# iya_ini_pcb_cetaknya.net
KiCad netlist of a schematic drawn in EAGLE
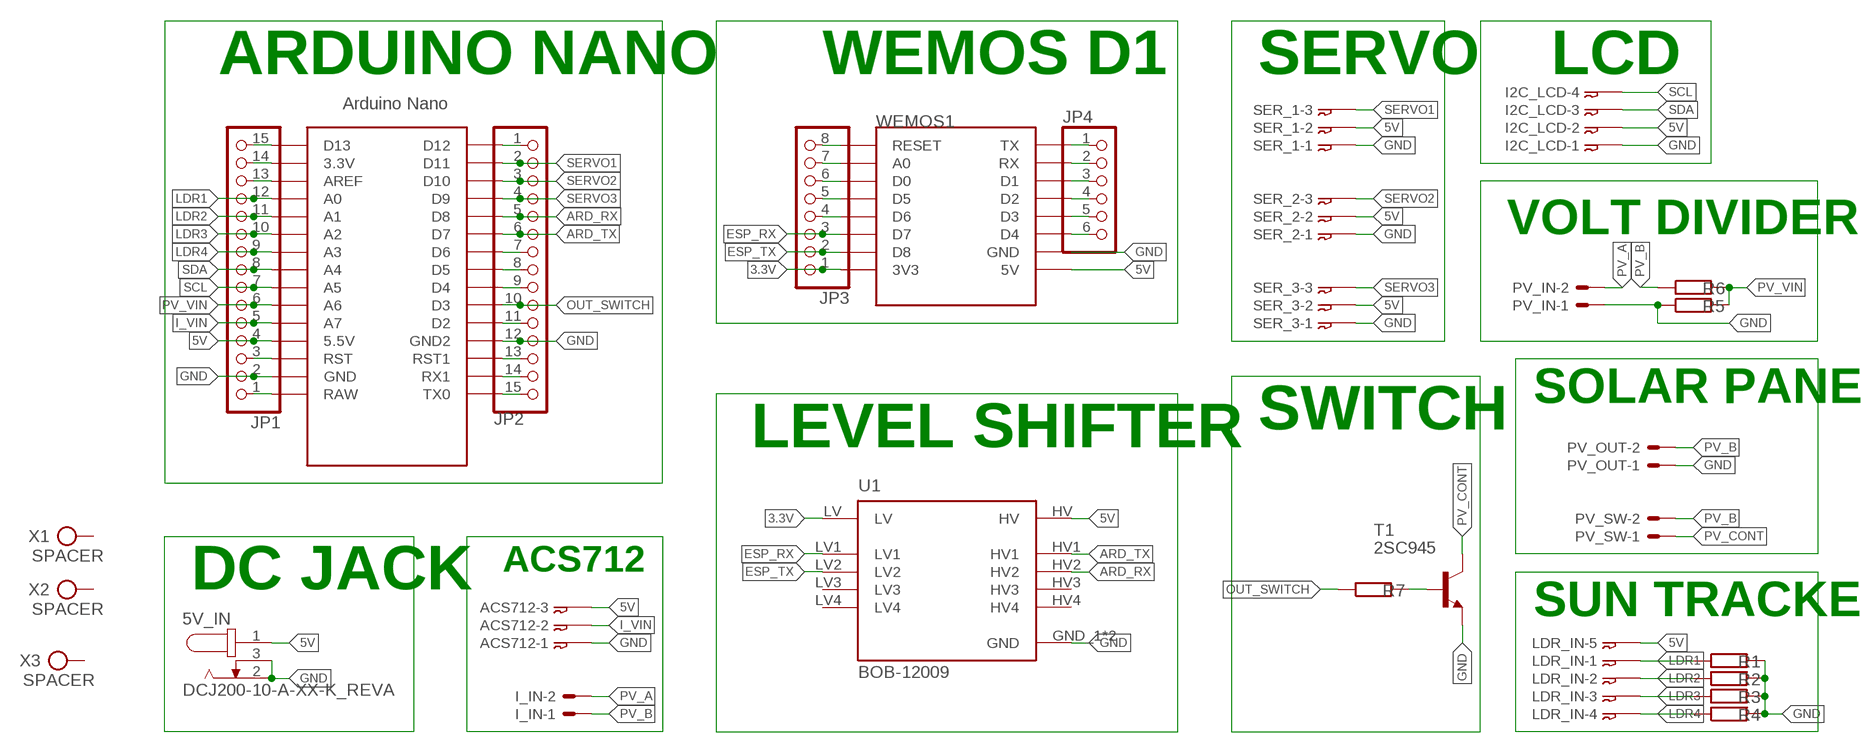
[diagram p0: schematic, sheet 1]

(export (version "E")
  (design (tool "Eeschema 10.0.6"))
  (components
    (comp (ref "5V_IN")
      (value "DCJ200-10-A-XX-K_REVA")
      (footprint "eagle-import:GCT_DCJ200-10-A-XX-K_REVA")
      (fields (field (name "MF") "Global Connector Technology") (field (name "MP") "DCJ200-10-A-K1-K"))
      (libsource (lib "eagle-import") (part "DCJ200-10-A-XX-K_REVA"))
    )
    (comp (ref "ACS712")
      (value "03-JST-B3B-XH-A")
      (footprint "eagle-import:B3B-XH")
      (libsource (lib "eagle-import") (part "03-JST-B3B-XH-A"))
    )
    (comp (ref "I2C_LCD")
      (value "04-JST-B4B-XH-A")
      (footprint "eagle-import:B4B-XH")
      (libsource (lib "eagle-import") (part "04-JST-B4B-XH-A"))
    )
    (comp (ref "I_IN")
      (value "MOLEX_2P_27-2021")
      (footprint "eagle-import:6410-02")
      (fields (field (name "MF") "MOLEX"))
      (libsource (lib "eagle-import") (part "MOLEX_2P_27-2021"))
    )
    (comp (ref "JP1")
      (value "PINHD-1X15")
      (footprint "eagle-import:1X15")
      (libsource (lib "eagle-import") (part "PINHD-1X15"))
    )
    (comp (ref "JP2")
      (value "PINHD-1X15")
      (footprint "eagle-import:1X15")
      (libsource (lib "eagle-import") (part "PINHD-1X15"))
    )
    (comp (ref "JP3")
      (value "PINHD-1X8")
      (footprint "eagle-import:1X08")
      (libsource (lib "eagle-import") (part "PINHD-1X8"))
    )
    (comp (ref "JP4")
      (value "PINHD-1X6")
      (footprint "eagle-import:1X06")
      (libsource (lib "eagle-import") (part "PINHD-1X6"))
    )
    (comp (ref "LDR_IN")
      (value "05-JST-B5B-XH-A")
      (footprint "eagle-import:B5B-XH")
      (libsource (lib "eagle-import") (part "05-JST-B5B-XH-A"))
    )
    (comp (ref "PV_IN")
      (value "MOLEX_2P_27-2021")
      (footprint "eagle-import:6410-02")
      (fields (field (name "MF") "MOLEX"))
      (libsource (lib "eagle-import") (part "MOLEX_2P_27-2021"))
    )
    (comp (ref "PV_OUT")
      (value "MOLEX_2P_27-2021")
      (footprint "eagle-import:6410-02")
      (fields (field (name "MF") "MOLEX"))
      (libsource (lib "eagle-import") (part "MOLEX_2P_27-2021"))
    )
    (comp (ref "PV_SW")
      (value "MOLEX_2P_27-2021")
      (footprint "eagle-import:6410-02")
      (fields (field (name "MF") "MOLEX"))
      (libsource (lib "eagle-import") (part "MOLEX_2P_27-2021"))
    )
    (comp (ref "R1")
      (value "R-EU_0207/2V")
      (footprint "eagle-import:0207_2V")
      (libsource (lib "eagle-import") (part "R-EU_0207/2V"))
    )
    (comp (ref "R2")
      (value "R-EU_0207/2V")
      (footprint "eagle-import:0207_2V")
      (libsource (lib "eagle-import") (part "R-EU_0207/2V"))
    )
    (comp (ref "R3")
      (value "R-EU_0207/2V")
      (footprint "eagle-import:0207_2V")
      (libsource (lib "eagle-import") (part "R-EU_0207/2V"))
    )
    (comp (ref "R4")
      (value "R-EU_0207/2V")
      (footprint "eagle-import:0207_2V")
      (libsource (lib "eagle-import") (part "R-EU_0207/2V"))
    )
    (comp (ref "R5")
      (value "R-EU_0207/10")
      (footprint "eagle-import:0207_10")
      (libsource (lib "eagle-import") (part "R-EU_0207/10"))
    )
    (comp (ref "R6")
      (value "R-EU_0207/10")
      (footprint "eagle-import:0207_10")
      (libsource (lib "eagle-import") (part "R-EU_0207/10"))
    )
    (comp (ref "R7")
      (value "R-EU_0207/10")
      (footprint "eagle-import:0207_10")
      (libsource (lib "eagle-import") (part "R-EU_0207/10"))
    )
    (comp (ref "SER_1")
      (value "03-JST-B3B-XH-A")
      (footprint "eagle-import:B3B-XH")
      (libsource (lib "eagle-import") (part "03-JST-B3B-XH-A"))
    )
    (comp (ref "SER_2")
      (value "03-JST-B3B-XH-A")
      (footprint "eagle-import:B3B-XH")
      (libsource (lib "eagle-import") (part "03-JST-B3B-XH-A"))
    )
    (comp (ref "SER_3")
      (value "03-JST-B3B-XH-A")
      (footprint "eagle-import:B3B-XH")
      (libsource (lib "eagle-import") (part "03-JST-B3B-XH-A"))
    )
    (comp (ref "T1")
      (value "2SC945")
      (footprint "eagle-import:TO92-ECB")
      (libsource (lib "eagle-import") (part "2SC945"))
    )
    (comp (ref "U$1")
      (value "NANO")
      (footprint "eagle-import:NANO")
      (libsource (lib "eagle-import") (part "NANO"))
    )
    (comp (ref "U1")
      (value "BOB-12009")
      (footprint "eagle-import:CONV_BOB-12009")
      (fields (field (name "MF") "SparkFun"))
      (libsource (lib "eagle-import") (part "BOB-12009"))
    )
    (comp (ref "WEMOS1")
      (value "WEMOS-D1-MINI")
      (footprint "eagle-import:WEMOS-D1-MINI")
      (libsource (lib "eagle-import") (part "WEMOS-D1-MINI"))
    )
    (comp (ref "X1")
      (value "SPACER")
      (footprint "eagle-import:SPACER")
      (libsource (lib "eagle-import") (part "SPACER"))
    )
    (comp (ref "X2")
      (value "SPACER")
      (footprint "eagle-import:SPACER")
      (libsource (lib "eagle-import") (part "SPACER"))
    )
    (comp (ref "X3")
      (value "SPACER")
      (footprint "eagle-import:SPACER")
      (libsource (lib "eagle-import") (part "SPACER"))
    )
  )
  (nets
    (net (code "1") (name "3.3V") (class "Default")
      (node (ref "JP3") (pin "1") (pinfunction "1_1") (pintype "passive"))
      (node (ref "U1") (pin "LV") (pinfunction "LV_LV") (pintype "bidirectional"))
      (node (ref "WEMOS1") (pin "3V3") (pinfunction "3V3_3V3") (pintype "bidirectional"))
    )
    (net (code "2") (name "5V") (class "Default")
      (node (ref "5V_IN") (pin "1") (pinfunction "1_1") (pintype "passive"))
      (node (ref "ACS712") (pin "P$3") (pinfunction "1_P$3") (pintype "passive"))
      (node (ref "I2C_LCD") (pin "P$2") (pinfunction "1_P$2") (pintype "passive"))
      (node (ref "JP1") (pin "4") (pinfunction "4_4") (pintype "passive"))
      (node (ref "LDR_IN") (pin "P$5") (pinfunction "1_P$5") (pintype "passive"))
      (node (ref "SER_1") (pin "P$2") (pinfunction "1_P$2") (pintype "passive"))
      (node (ref "SER_2") (pin "P$2") (pinfunction "1_P$2") (pintype "passive"))
      (node (ref "SER_3") (pin "P$2") (pinfunction "1_P$2") (pintype "passive"))
      (node (ref "U$1") (pin "5V") (pinfunction "5.5V_5V") (pintype "bidirectional"))
      (node (ref "U1") (pin "HV") (pinfunction "HV_HV") (pintype "bidirectional"))
      (node (ref "WEMOS1") (pin "5V") (pinfunction "5V_5V") (pintype "bidirectional"))
    )
    (net (code "3") (name "ARD_RX") (class "Default")
      (node (ref "JP2") (pin "5") (pinfunction "5_5") (pintype "passive"))
      (node (ref "U$1") (pin "D8") (pinfunction "D8_D8") (pintype "bidirectional"))
      (node (ref "U1") (pin "HV2") (pinfunction "HV2_HV2") (pintype "bidirectional"))
    )
    (net (code "4") (name "ARD_TX") (class "Default")
      (node (ref "JP2") (pin "6") (pinfunction "6_6") (pintype "passive"))
      (node (ref "U$1") (pin "D7") (pinfunction "D7_D7") (pintype "bidirectional"))
      (node (ref "U1") (pin "HV1") (pinfunction "HV1_HV1") (pintype "bidirectional"))
    )
    (net (code "5") (name "ESP_RX") (class "Default")
      (node (ref "JP3") (pin "3") (pinfunction "3_3") (pintype "passive"))
      (node (ref "U1") (pin "LV1") (pinfunction "LV1_LV1") (pintype "bidirectional"))
      (node (ref "WEMOS1") (pin "D7") (pinfunction "D7_D7") (pintype "bidirectional"))
    )
    (net (code "6") (name "ESP_TX") (class "Default")
      (node (ref "JP3") (pin "2") (pinfunction "2_2") (pintype "passive"))
      (node (ref "U1") (pin "LV2") (pinfunction "LV2_LV2") (pintype "bidirectional"))
      (node (ref "WEMOS1") (pin "D8") (pinfunction "D8_D8") (pintype "bidirectional"))
    )
    (net (code "7") (name "GND") (class "Default")
      (node (ref "5V_IN") (pin "2") (pinfunction "2_2") (pintype "passive"))
      (node (ref "5V_IN") (pin "3") (pinfunction "3_3") (pintype "passive"))
      (node (ref "ACS712") (pin "P$1") (pinfunction "1_P$1") (pintype "passive"))
      (node (ref "I2C_LCD") (pin "P$1") (pinfunction "1_P$1") (pintype "passive"))
      (node (ref "JP1") (pin "2") (pinfunction "2_2") (pintype "passive"))
      (node (ref "JP2") (pin "12") (pinfunction "12_12") (pintype "passive"))
      (node (ref "PV_IN") (pin "1") (pinfunction "S_1") (pintype "passive"))
      (node (ref "PV_OUT") (pin "1") (pinfunction "S_1") (pintype "passive"))
      (node (ref "R1") (pin "2") (pinfunction "2_2") (pintype "passive"))
      (node (ref "R2") (pin "2") (pinfunction "2_2") (pintype "passive"))
      (node (ref "R3") (pin "2") (pinfunction "2_2") (pintype "passive"))
      (node (ref "R4") (pin "2") (pinfunction "2_2") (pintype "passive"))
      (node (ref "R5") (pin "1") (pinfunction "1_1") (pintype "passive"))
      (node (ref "SER_1") (pin "P$1") (pinfunction "1_P$1") (pintype "passive"))
      (node (ref "SER_2") (pin "P$1") (pinfunction "1_P$1") (pintype "passive"))
      (node (ref "SER_3") (pin "P$1") (pinfunction "1_P$1") (pintype "passive"))
      (node (ref "T1") (pin "E") (pinfunction "E_E") (pintype "passive"))
      (node (ref "U$1") (pin "GND") (pinfunction "GND_GND") (pintype "bidirectional"))
      (node (ref "U$1") (pin "GND1") (pinfunction "GND2_GND1") (pintype "bidirectional"))
      (node (ref "U1") (pin "GND_1") (pinfunction "GND_GND_1") (pintype "power_in"))
      (node (ref "U1") (pin "GND_2") (pinfunction "GND_GND_2") (pintype "power_in"))
      (node (ref "WEMOS1") (pin "GND") (pinfunction "GND_GND") (pintype "bidirectional"))
    )
    (net (code "8") (name "I_VIN") (class "Default")
      (node (ref "ACS712") (pin "P$2") (pinfunction "1_P$2") (pintype "passive"))
      (node (ref "JP1") (pin "5") (pinfunction "5_5") (pintype "passive"))
      (node (ref "U$1") (pin "A7") (pinfunction "A7_A7") (pintype "bidirectional"))
    )
    (net (code "9") (name "LDR1") (class "Default")
      (node (ref "JP1") (pin "12") (pinfunction "12_12") (pintype "passive"))
      (node (ref "LDR_IN") (pin "P$1") (pinfunction "1_P$1") (pintype "passive"))
      (node (ref "R1") (pin "1") (pinfunction "1_1") (pintype "passive"))
      (node (ref "U$1") (pin "A0") (pinfunction "A0_A0") (pintype "bidirectional"))
    )
    (net (code "10") (name "LDR2") (class "Default")
      (node (ref "JP1") (pin "11") (pinfunction "11_11") (pintype "passive"))
      (node (ref "LDR_IN") (pin "P$2") (pinfunction "1_P$2") (pintype "passive"))
      (node (ref "R2") (pin "1") (pinfunction "1_1") (pintype "passive"))
      (node (ref "U$1") (pin "A1") (pinfunction "A1_A1") (pintype "bidirectional"))
    )
    (net (code "11") (name "LDR3") (class "Default")
      (node (ref "JP1") (pin "10") (pinfunction "10_10") (pintype "passive"))
      (node (ref "LDR_IN") (pin "P$3") (pinfunction "1_P$3") (pintype "passive"))
      (node (ref "R3") (pin "1") (pinfunction "1_1") (pintype "passive"))
      (node (ref "U$1") (pin "A2") (pinfunction "A2_A2") (pintype "bidirectional"))
    )
    (net (code "12") (name "LDR4") (class "Default")
      (node (ref "JP1") (pin "9") (pinfunction "9_9") (pintype "passive"))
      (node (ref "LDR_IN") (pin "P$4") (pinfunction "1_P$4") (pintype "passive"))
      (node (ref "R4") (pin "1") (pinfunction "1_1") (pintype "passive"))
      (node (ref "U$1") (pin "A3") (pinfunction "A3_A3") (pintype "bidirectional"))
    )
    (net (code "13") (name "Net-(JP1-Pad1)") (class "Default")
      (node (ref "JP1") (pin "1") (pinfunction "1_1") (pintype "passive"))
      (node (ref "U$1") (pin "RAW") (pinfunction "RAW_RAW") (pintype "bidirectional"))
    )
    (net (code "14") (name "Net-(JP1-Pad3)") (class "Default")
      (node (ref "JP1") (pin "3") (pinfunction "3_3") (pintype "passive"))
      (node (ref "U$1") (pin "RST") (pinfunction "RST_RST") (pintype "bidirectional"))
    )
    (net (code "15") (name "Net-(JP1-Pad13)") (class "Default")
      (node (ref "JP1") (pin "13") (pinfunction "13_13") (pintype "passive"))
      (node (ref "U$1") (pin "AREF") (pinfunction "AREF_AREF") (pintype "bidirectional"))
    )
    (net (code "16") (name "Net-(JP1-Pad14)") (class "Default")
      (node (ref "JP1") (pin "14") (pinfunction "14_14") (pintype "passive"))
      (node (ref "U$1") (pin "3.3V") (pinfunction "3.3V_3.3V") (pintype "bidirectional"))
    )
    (net (code "17") (name "Net-(JP1-Pad15)") (class "Default")
      (node (ref "JP1") (pin "15") (pinfunction "15_15") (pintype "passive"))
      (node (ref "U$1") (pin "D13") (pinfunction "D13_D13") (pintype "bidirectional"))
    )
    (net (code "18") (name "Net-(JP2-Pad1)") (class "Default")
      (node (ref "JP2") (pin "1") (pinfunction "1_1") (pintype "passive"))
      (node (ref "U$1") (pin "D12") (pinfunction "D12_D12") (pintype "bidirectional"))
    )
    (net (code "19") (name "Net-(JP2-Pad7)") (class "Default")
      (node (ref "JP2") (pin "7") (pinfunction "7_7") (pintype "passive"))
      (node (ref "U$1") (pin "D6") (pinfunction "D6_D6") (pintype "bidirectional"))
    )
    (net (code "20") (name "Net-(JP2-Pad8)") (class "Default")
      (node (ref "JP2") (pin "8") (pinfunction "8_8") (pintype "passive"))
      (node (ref "U$1") (pin "D5") (pinfunction "D5_D5") (pintype "bidirectional"))
    )
    (net (code "21") (name "Net-(JP2-Pad9)") (class "Default")
      (node (ref "JP2") (pin "9") (pinfunction "9_9") (pintype "passive"))
      (node (ref "U$1") (pin "D4") (pinfunction "D4_D4") (pintype "bidirectional"))
    )
    (net (code "22") (name "Net-(JP2-Pad11)") (class "Default")
      (node (ref "JP2") (pin "11") (pinfunction "11_11") (pintype "passive"))
      (node (ref "U$1") (pin "D2") (pinfunction "D2_D2") (pintype "bidirectional"))
    )
    (net (code "23") (name "Net-(JP2-Pad13)") (class "Default")
      (node (ref "JP2") (pin "13") (pinfunction "13_13") (pintype "passive"))
      (node (ref "U$1") (pin "RST1") (pinfunction "RST1_RST1") (pintype "bidirectional"))
    )
    (net (code "24") (name "Net-(JP2-Pad14)") (class "Default")
      (node (ref "JP2") (pin "14") (pinfunction "14_14") (pintype "passive"))
      (node (ref "U$1") (pin "RX1") (pinfunction "RX1_RX1") (pintype "bidirectional"))
    )
    (net (code "25") (name "Net-(JP2-Pad15)") (class "Default")
      (node (ref "JP2") (pin "15") (pinfunction "15_15") (pintype "passive"))
      (node (ref "U$1") (pin "TX0") (pinfunction "TX0_TX0") (pintype "bidirectional"))
    )
    (net (code "26") (name "Net-(JP3-Pad4)") (class "Default")
      (node (ref "JP3") (pin "4") (pinfunction "4_4") (pintype "passive"))
      (node (ref "WEMOS1") (pin "D6") (pinfunction "D6_D6") (pintype "bidirectional"))
    )
    (net (code "27") (name "Net-(JP3-Pad5)") (class "Default")
      (node (ref "JP3") (pin "5") (pinfunction "5_5") (pintype "passive"))
      (node (ref "WEMOS1") (pin "D5") (pinfunction "D5_D5") (pintype "bidirectional"))
    )
    (net (code "28") (name "Net-(JP3-Pad6)") (class "Default")
      (node (ref "JP3") (pin "6") (pinfunction "6_6") (pintype "passive"))
      (node (ref "WEMOS1") (pin "D0") (pinfunction "D0_D0") (pintype "bidirectional"))
    )
    (net (code "29") (name "Net-(JP3-Pad7)") (class "Default")
      (node (ref "JP3") (pin "7") (pinfunction "7_7") (pintype "passive"))
      (node (ref "WEMOS1") (pin "A0") (pinfunction "A0_A0") (pintype "bidirectional"))
    )
    (net (code "30") (name "Net-(JP3-Pad8)") (class "Default")
      (node (ref "JP3") (pin "8") (pinfunction "8_8") (pintype "passive"))
      (node (ref "WEMOS1") (pin "RESET") (pinfunction "RESET_RESET") (pintype "bidirectional"))
    )
    (net (code "31") (name "Net-(JP4-Pad1)") (class "Default")
      (node (ref "JP4") (pin "1") (pinfunction "1_1") (pintype "passive"))
      (node (ref "WEMOS1") (pin "TX") (pinfunction "TX_TX") (pintype "bidirectional"))
    )
    (net (code "32") (name "Net-(JP4-Pad2)") (class "Default")
      (node (ref "JP4") (pin "2") (pinfunction "2_2") (pintype "passive"))
      (node (ref "WEMOS1") (pin "RX") (pinfunction "RX_RX") (pintype "bidirectional"))
    )
    (net (code "33") (name "Net-(JP4-Pad3)") (class "Default")
      (node (ref "JP4") (pin "3") (pinfunction "3_3") (pintype "passive"))
      (node (ref "WEMOS1") (pin "D1") (pinfunction "D1_D1") (pintype "bidirectional"))
    )
    (net (code "34") (name "Net-(JP4-Pad4)") (class "Default")
      (node (ref "JP4") (pin "4") (pinfunction "4_4") (pintype "passive"))
      (node (ref "WEMOS1") (pin "D2") (pinfunction "D2_D2") (pintype "bidirectional"))
    )
    (net (code "35") (name "Net-(JP4-Pad5)") (class "Default")
      (node (ref "JP4") (pin "5") (pinfunction "5_5") (pintype "passive"))
      (node (ref "WEMOS1") (pin "D3") (pinfunction "D3_D3") (pintype "bidirectional"))
    )
    (net (code "36") (name "Net-(JP4-Pad6)") (class "Default")
      (node (ref "JP4") (pin "6") (pinfunction "6_6") (pintype "passive"))
      (node (ref "WEMOS1") (pin "D4") (pinfunction "D4_D4") (pintype "bidirectional"))
    )
    (net (code "37") (name "Net-(R7-Pad2)") (class "Default")
      (node (ref "R7") (pin "2") (pinfunction "2_2") (pintype "passive"))
      (node (ref "T1") (pin "B") (pinfunction "B_B") (pintype "passive"))
    )
    (net (code "38") (name "OUT_SWITCH") (class "Default")
      (node (ref "JP2") (pin "10") (pinfunction "10_10") (pintype "passive"))
      (node (ref "R7") (pin "1") (pinfunction "1_1") (pintype "passive"))
      (node (ref "U$1") (pin "D3") (pinfunction "D3_D3") (pintype "bidirectional"))
    )
    (net (code "39") (name "PV_A") (class "Default")
      (node (ref "I_IN") (pin "2") (pinfunction "S_2") (pintype "passive"))
      (node (ref "PV_IN") (pin "2") (pinfunction "S_2") (pintype "passive"))
    )
    (net (code "40") (name "PV_B") (class "Default")
      (node (ref "I_IN") (pin "1") (pinfunction "S_1") (pintype "passive"))
      (node (ref "PV_OUT") (pin "2") (pinfunction "S_2") (pintype "passive"))
      (node (ref "PV_SW") (pin "2") (pinfunction "S_2") (pintype "passive"))
      (node (ref "R6") (pin "1") (pinfunction "1_1") (pintype "passive"))
    )
    (net (code "41") (name "PV_CONT") (class "Default")
      (node (ref "PV_SW") (pin "1") (pinfunction "S_1") (pintype "passive"))
      (node (ref "T1") (pin "C") (pinfunction "C_C") (pintype "passive"))
    )
    (net (code "42") (name "PV_VIN") (class "Default")
      (node (ref "JP1") (pin "6") (pinfunction "6_6") (pintype "passive"))
      (node (ref "R5") (pin "2") (pinfunction "2_2") (pintype "passive"))
      (node (ref "R6") (pin "2") (pinfunction "2_2") (pintype "passive"))
      (node (ref "U$1") (pin "A6") (pinfunction "A6_A6") (pintype "bidirectional"))
    )
    (net (code "43") (name "SCL") (class "Default")
      (node (ref "I2C_LCD") (pin "P$4") (pinfunction "1_P$4") (pintype "passive"))
      (node (ref "JP1") (pin "7") (pinfunction "7_7") (pintype "passive"))
      (node (ref "U$1") (pin "A5") (pinfunction "A5_A5") (pintype "bidirectional"))
    )
    (net (code "44") (name "SDA") (class "Default")
      (node (ref "I2C_LCD") (pin "P$3") (pinfunction "1_P$3") (pintype "passive"))
      (node (ref "JP1") (pin "8") (pinfunction "8_8") (pintype "passive"))
      (node (ref "U$1") (pin "A4") (pinfunction "A4_A4") (pintype "bidirectional"))
    )
    (net (code "45") (name "SERVO1") (class "Default")
      (node (ref "JP2") (pin "2") (pinfunction "2_2") (pintype "passive"))
      (node (ref "SER_1") (pin "P$3") (pinfunction "1_P$3") (pintype "passive"))
      (node (ref "U$1") (pin "D11") (pinfunction "D11_D11") (pintype "bidirectional"))
    )
    (net (code "46") (name "SERVO2") (class "Default")
      (node (ref "JP2") (pin "3") (pinfunction "3_3") (pintype "passive"))
      (node (ref "SER_2") (pin "P$3") (pinfunction "1_P$3") (pintype "passive"))
      (node (ref "U$1") (pin "D10") (pinfunction "D10_D10") (pintype "bidirectional"))
    )
    (net (code "47") (name "SERVO3") (class "Default")
      (node (ref "JP2") (pin "4") (pinfunction "4_4") (pintype "passive"))
      (node (ref "SER_3") (pin "P$3") (pinfunction "1_P$3") (pintype "passive"))
      (node (ref "U$1") (pin "D9") (pinfunction "D9_D9") (pintype "bidirectional"))
    )
    (net (code "48") (name "unconnected-(U$1-PadICSP1)") (class "Default")
      (node (ref "U$1") (pin "ICSP1") (pinfunction "ICSP1_ICSP1") (pintype "bidirectional"))
    )
    (net (code "49") (name "unconnected-(U$1-PadICSP2)") (class "Default")
      (node (ref "U$1") (pin "ICSP2") (pinfunction "ICSP2_ICSP2") (pintype "bidirectional"))
    )
    (net (code "50") (name "unconnected-(U$1-PadICSP3)") (class "Default")
      (node (ref "U$1") (pin "ICSP3") (pinfunction "ICSP3_ICSP3") (pintype "bidirectional"))
    )
    (net (code "51") (name "unconnected-(U$1-PadICSP4)") (class "Default")
      (node (ref "U$1") (pin "ICSP4") (pinfunction "ICSP4_ICSP4") (pintype "bidirectional"))
    )
    (net (code "52") (name "unconnected-(U$1-PadICSP5)") (class "Default")
      (node (ref "U$1") (pin "ICSP5") (pinfunction "ICSP5_ICSP5") (pintype "bidirectional"))
    )
    (net (code "53") (name "unconnected-(U$1-PadICSP6)") (class "Default")
      (node (ref "U$1") (pin "ICSP6") (pinfunction "ICSP6_ICSP6") (pintype "bidirectional"))
    )
    (net (code "54") (name "unconnected-(U1-PadHV3)") (class "Default")
      (node (ref "U1") (pin "HV3") (pinfunction "HV3_HV3") (pintype "bidirectional"))
    )
    (net (code "55") (name "unconnected-(U1-PadHV4)") (class "Default")
      (node (ref "U1") (pin "HV4") (pinfunction "HV4_HV4") (pintype "bidirectional"))
    )
    (net (code "56") (name "unconnected-(U1-PadLV3)") (class "Default")
      (node (ref "U1") (pin "LV3") (pinfunction "LV3_LV3") (pintype "bidirectional"))
    )
    (net (code "57") (name "unconnected-(U1-PadLV4)") (class "Default")
      (node (ref "U1") (pin "LV4") (pinfunction "LV4_LV4") (pintype "bidirectional"))
    )
    (net (code "58") (name "unconnected-(X1-PadX)") (class "Default")
      (node (ref "X1") (pin "X") (pinfunction "X_X") (pintype "passive"))
    )
    (net (code "59") (name "unconnected-(X2-PadX)") (class "Default")
      (node (ref "X2") (pin "X") (pinfunction "X_X") (pintype "passive"))
    )
    (net (code "60") (name "unconnected-(X3-PadX)") (class "Default")
      (node (ref "X3") (pin "X") (pinfunction "X_X") (pintype "passive"))
    )
  )
)
